# WiFi.net
KiCad netlist of a schematic drawn in Altium Designer
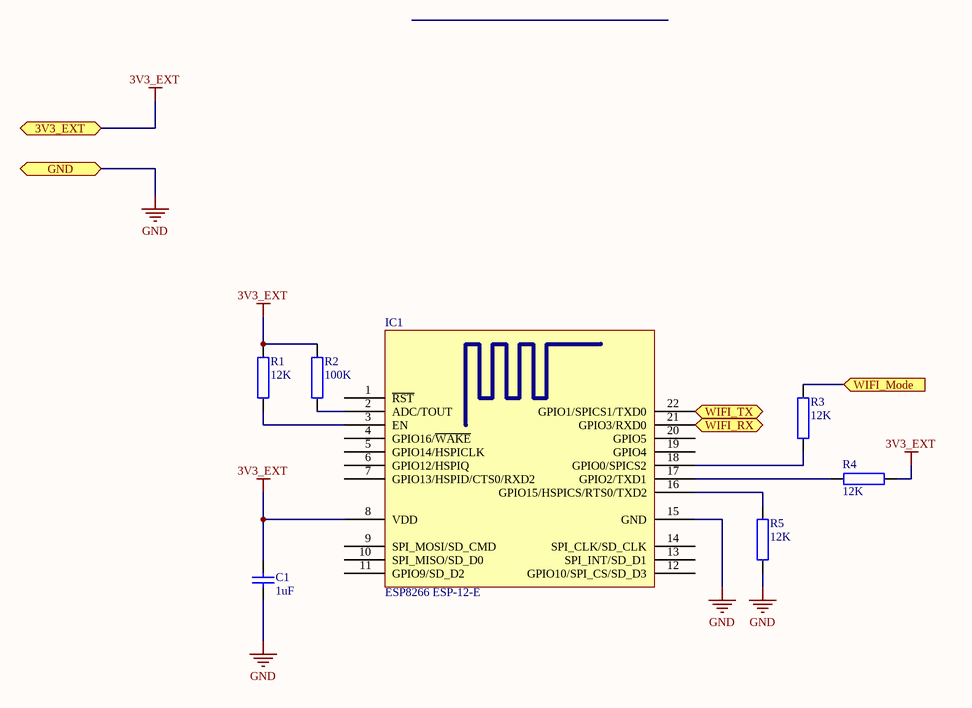
[diagram p0: WiFi.SchDoc]

(export (version "E")
  (design (tool "Eeschema 10.0.6"))
  (components
    (comp (ref "C1")
      (value "1uF")
      (footprint "C0603")
      (description "Capacitor (Semiconductor SIM Model)")
      (fields (field (name "PUBLISHER") "Altium Limited"))
      (libsource (lib "Quadcopter") (part "Cap"))
    )
    (comp (ref "IC1")
      (value "ESP8266 ESP-12-E")
      (footprint "Quadcopter:ESP_12_E")
      (libsource (lib "Quadcopter") (part "ESP8266 ESP-12-E"))
    )
    (comp (ref "R1")
      (value "12K")
      (footprint "R0603")
      (description "Resistor")
      (fields (field (name "PUBLISHER") "Altium Limited"))
      (libsource (lib "Quadcopter") (part "Res3"))
    )
    (comp (ref "R2")
      (value "100K")
      (footprint "R0603")
      (description "Resistor")
      (fields (field (name "PUBLISHER") "Altium Limited"))
      (libsource (lib "Quadcopter") (part "Res3"))
    )
    (comp (ref "R3")
      (value "12K")
      (footprint "R0603")
      (description "Resistor")
      (fields (field (name "PUBLISHER") "Altium Limited"))
      (libsource (lib "Quadcopter") (part "Res3"))
    )
    (comp (ref "R4")
      (value "12K")
      (footprint "R0603")
      (description "Resistor")
      (fields (field (name "PUBLISHER") "Altium Limited"))
      (libsource (lib "Quadcopter") (part "Res3"))
    )
    (comp (ref "R5")
      (value "12K")
      (footprint "R0603")
      (description "Resistor")
      (fields (field (name "PUBLISHER") "Altium Limited"))
      (libsource (lib "Quadcopter") (part "Res3"))
    )
  )
  (nets
    (net (code "1") (name "/WIFI_Mode") (class "Default")
      (node (ref "R3") (pin "1") (pinfunction "1_1") (pintype "passive"))
    )
    (net (code "2") (name "/WIFI_RX") (class "Default")
      (node (ref "IC1") (pin "21") (pinfunction "GPIO3/RXD0_21") (pintype "passive"))
    )
    (net (code "3") (name "/WIFI_TX") (class "Default")
      (node (ref "IC1") (pin "22") (pinfunction "GPIO1/SPICS1/TXD0_22") (pintype "passive"))
    )
    (net (code "4") (name "3V3_EXT") (class "Default")
      (node (ref "C1") (pin "2") (pinfunction "2_2") (pintype "passive"))
      (node (ref "IC1") (pin "8") (pinfunction "VDD_8") (pintype "passive"))
      (node (ref "R1") (pin "2") (pinfunction "2_2") (pintype "passive"))
      (node (ref "R2") (pin "2") (pinfunction "2_2") (pintype "passive"))
      (node (ref "R4") (pin "1") (pinfunction "1_1") (pintype "passive"))
    )
    (net (code "5") (name "GND") (class "Default")
      (node (ref "C1") (pin "1") (pinfunction "1_1") (pintype "passive"))
      (node (ref "IC1") (pin "15") (pinfunction "GND_15") (pintype "passive"))
      (node (ref "R5") (pin "2") (pinfunction "2_2") (pintype "passive"))
    )
    (net (code "6") (name "Net-(IC1-ADC{slash}TOUT)") (class "Default")
      (node (ref "IC1") (pin "2") (pinfunction "ADC/TOUT_2") (pintype "passive"))
      (node (ref "R2") (pin "1") (pinfunction "1_1") (pintype "passive"))
    )
    (net (code "7") (name "Net-(IC1-EN)") (class "Default")
      (node (ref "IC1") (pin "3") (pinfunction "EN_3") (pintype "passive"))
      (node (ref "R1") (pin "1") (pinfunction "1_1") (pintype "passive"))
    )
    (net (code "8") (name "Net-(IC1-GPIO0{slash}SPICS2)") (class "Default")
      (node (ref "IC1") (pin "18") (pinfunction "GPIO0/SPICS2_18") (pintype "passive"))
      (node (ref "R3") (pin "2") (pinfunction "2_2") (pintype "passive"))
    )
    (net (code "9") (name "Net-(IC1-GPIO2{slash}TXD1)") (class "Default")
      (node (ref "IC1") (pin "17") (pinfunction "GPIO2/TXD1_17") (pintype "passive"))
      (node (ref "R4") (pin "2") (pinfunction "2_2") (pintype "passive"))
    )
    (net (code "10") (name "Net-(IC1-GPIO15{slash}HSPICS{slash}RTS0{slash}TXD2)") (class "Default")
      (node (ref "IC1") (pin "16") (pinfunction "GPIO15/HSPICS/RTS0/TXD2_16") (pintype "passive"))
      (node (ref "R5") (pin "1") (pinfunction "1_1") (pintype "passive"))
    )
    (net (code "11") (name "unconnected-(IC1-GPIO4-Pad19)") (class "Default")
      (node (ref "IC1") (pin "19") (pinfunction "GPIO4_19") (pintype "passive"))
    )
    (net (code "12") (name "unconnected-(IC1-GPIO5-Pad20)") (class "Default")
      (node (ref "IC1") (pin "20") (pinfunction "GPIO5_20") (pintype "passive"))
    )
    (net (code "13") (name "unconnected-(IC1-GPIO9{slash}SD_D2-Pad11)") (class "Default")
      (node (ref "IC1") (pin "11") (pinfunction "GPIO9/SD_D2_11") (pintype "passive"))
    )
    (net (code "14") (name "unconnected-(IC1-GPIO10{slash}SPI_CS{slash}SD_D3-Pad12)") (class "Default")
      (node (ref "IC1") (pin "12") (pinfunction "GPIO10/SPI_CS/SD_D3_12") (pintype "passive"))
    )
    (net (code "15") (name "unconnected-(IC1-GPIO12{slash}HSPIQ-Pad6)") (class "Default")
      (node (ref "IC1") (pin "6") (pinfunction "GPIO12/HSPIQ_6") (pintype "passive"))
    )
    (net (code "16") (name "unconnected-(IC1-GPIO13{slash}HSPID{slash}CTS0{slash}RXD2-Pad7)") (class "Default")
      (node (ref "IC1") (pin "7") (pinfunction "GPIO13/HSPID/CTS0/RXD2_7") (pintype "passive"))
    )
    (net (code "17") (name "unconnected-(IC1-GPIO14{slash}HSPICLK-Pad5)") (class "Default")
      (node (ref "IC1") (pin "5") (pinfunction "GPIO14/HSPICLK_5") (pintype "passive"))
    )
    (net (code "18") (name "unconnected-(IC1-GPIO16{slash}~{WAKE}-Pad4)") (class "Default")
      (node (ref "IC1") (pin "4") (pinfunction "GPIO16/~{WAKE}_4") (pintype "passive"))
    )
    (net (code "19") (name "unconnected-(IC1-SPI_CLK{slash}SD_CLK-Pad14)") (class "Default")
      (node (ref "IC1") (pin "14") (pinfunction "SPI_CLK/SD_CLK_14") (pintype "passive"))
    )
    (net (code "20") (name "unconnected-(IC1-SPI_INT{slash}SD_D1-Pad13)") (class "Default")
      (node (ref "IC1") (pin "13") (pinfunction "SPI_INT/SD_D1_13") (pintype "passive"))
    )
    (net (code "21") (name "unconnected-(IC1-SPI_MISO{slash}SD_D0-Pad10)") (class "Default")
      (node (ref "IC1") (pin "10") (pinfunction "SPI_MISO/SD_D0_10") (pintype "passive"))
    )
    (net (code "22") (name "unconnected-(IC1-SPI_MOSI{slash}SD_CMD-Pad9)") (class "Default")
      (node (ref "IC1") (pin "9") (pinfunction "SPI_MOSI/SD_CMD_9") (pintype "passive"))
    )
    (net (code "23") (name "unconnected-(IC1-~{RST}-Pad1)") (class "Default")
      (node (ref "IC1") (pin "1") (pinfunction "~{RST}_1") (pintype "passive"))
    )
  )
)
